# SunnyBuddy.net
KiCad netlist of a schematic drawn in EAGLE
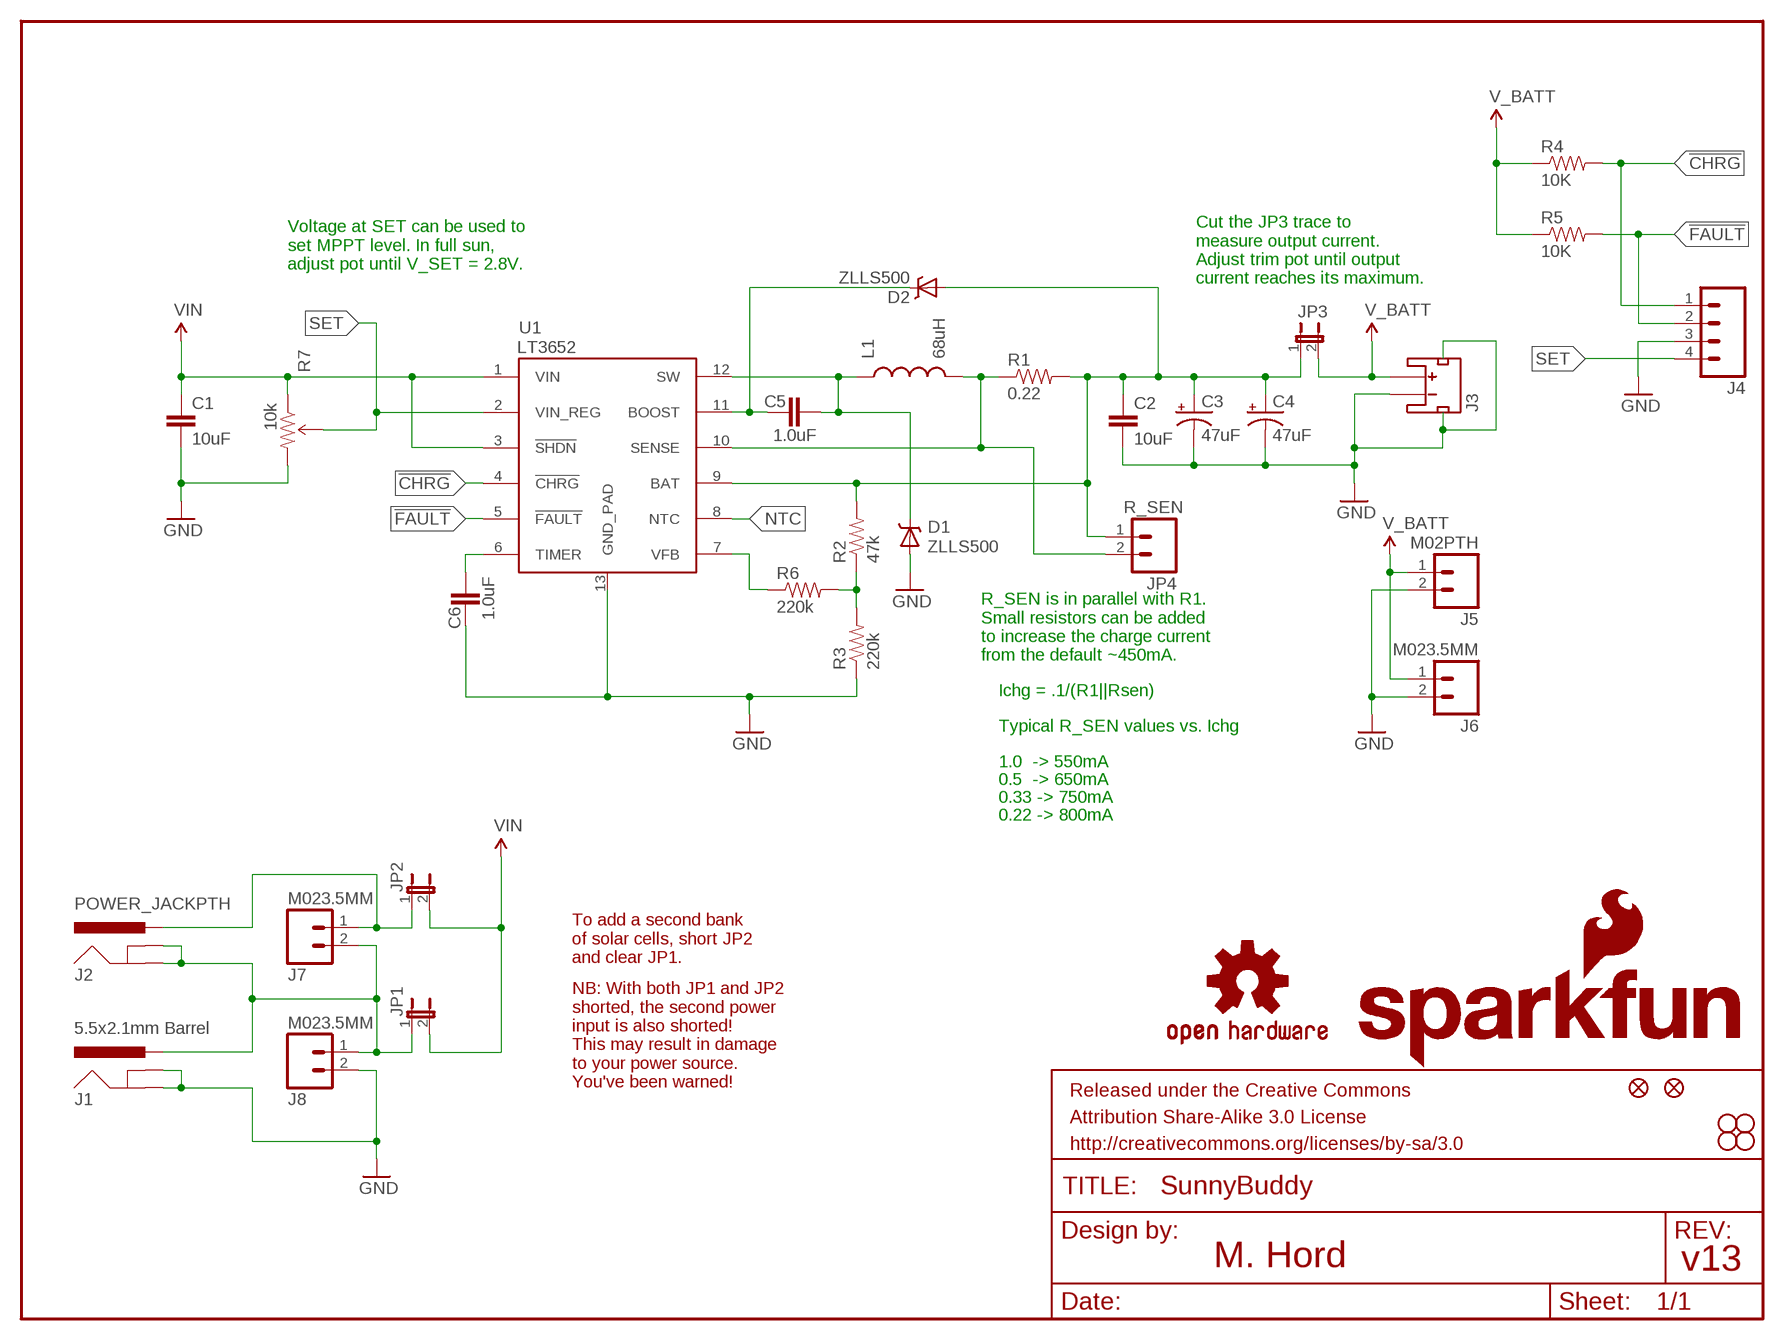
[diagram p0: schematic, sheet 1]

(export (version "E")
  (design (tool "Eeschema 10.0.6"))
  (components
    (comp (ref "C1")
      (value "10uF")
      (footprint "eagle-import:1210")
      (libsource (lib "eagle-import") (part "10UF50V20%(1210)"))
    )
    (comp (ref "C2")
      (value "10uF")
      (footprint "eagle-import:1206")
      (libsource (lib "eagle-import") (part "10UF-6.3V-20%(1206)"))
    )
    (comp (ref "C3")
      (value "47uF")
      (footprint "eagle-import:EIA3528")
      (libsource (lib "eagle-import") (part "47UF-TANT"))
    )
    (comp (ref "C4")
      (value "47uF")
      (footprint "eagle-import:EIA3528")
      (libsource (lib "eagle-import") (part "47UF-TANT"))
    )
    (comp (ref "C5")
      (value "1.0uF")
      (footprint "eagle-import:0603-CAP")
      (libsource (lib "eagle-import") (part "1.0UF-16V-10%(0603)"))
    )
    (comp (ref "C6")
      (value "1.0uF")
      (footprint "eagle-import:0603-CAP")
      (libsource (lib "eagle-import") (part "1.0UF-16V-10%(0603)"))
    )
    (comp (ref "D1")
      (value "ZLLS500")
      (footprint "eagle-import:SOT23")
      (libsource (lib "eagle-import") (part "ZLLS500ZLLS500"))
    )
    (comp (ref "D2")
      (value "ZLLS500")
      (footprint "eagle-import:SOT23")
      (libsource (lib "eagle-import") (part "ZLLS500ZLLS500"))
    )
    (comp (ref "FID1")
      (value "FIDUCIAL1X2")
      (footprint "eagle-import:FIDUCIAL-1X2")
      (libsource (lib "eagle-import") (part "FIDUCIAL1X2"))
    )
    (comp (ref "FID2")
      (value "FIDUCIAL1X2")
      (footprint "eagle-import:FIDUCIAL-1X2")
      (libsource (lib "eagle-import") (part "FIDUCIAL1X2"))
    )
    (comp (ref "FRAME1")
      (value "FRAME-LETTER")
      (footprint "eagle-import:CREATIVE_COMMONS")
      (libsource (lib "eagle-import") (part "FRAME-LETTER"))
    )
    (comp (ref "J1")
      (value "5.5x2.1mm Barrel")
      (footprint "eagle-import:POWER_JACK_SMD")
      (libsource (lib "eagle-import") (part "POWER_JACKSMD"))
    )
    (comp (ref "J2")
      (value "POWER_JACKPTH")
      (footprint "eagle-import:POWER_JACK_PTH")
      (libsource (lib "eagle-import") (part "POWER_JACKPTH"))
    )
    (comp (ref "J3")
      (value "JST_2MM_MALE")
      (footprint "eagle-import:JST-2-SMD")
      (libsource (lib "eagle-import") (part "JST_2MM_MALE"))
    )
    (comp (ref "J4")
      (value "M04PTH")
      (footprint "eagle-import:1X04")
      (libsource (lib "eagle-import") (part "M04PTH"))
    )
    (comp (ref "J5")
      (value "M02PTH")
      (footprint "eagle-import:1X02")
      (libsource (lib "eagle-import") (part "M02PTH"))
    )
    (comp (ref "J6")
      (value "M023.5MM")
      (footprint "eagle-import:SCREWTERMINAL-3.5MM-2")
      (libsource (lib "eagle-import") (part "M023.5MM"))
    )
    (comp (ref "J7")
      (value "M023.5MM")
      (footprint "eagle-import:SCREWTERMINAL-3.5MM-2")
      (libsource (lib "eagle-import") (part "M023.5MM"))
    )
    (comp (ref "J8")
      (value "M023.5MM")
      (footprint "eagle-import:SCREWTERMINAL-3.5MM-2")
      (libsource (lib "eagle-import") (part "M023.5MM"))
    )
    (comp (ref "JP1")
      (value "JUMPER-2SMD-NC")
      (footprint "eagle-import:SJ_2S")
      (libsource (lib "eagle-import") (part "JUMPER-2SMD-NC"))
    )
    (comp (ref "JP2")
      (value "JUMPER-2SMD-NO")
      (footprint "eagle-import:SJ_2S-NO")
      (libsource (lib "eagle-import") (part "JUMPER-2SMD-NO"))
    )
    (comp (ref "JP3")
      (value "JUMPER-PTH-2-NC")
      (footprint "eagle-import:PTH-JUMPER-NC_BOTTOM_NO_SILK")
      (libsource (lib "eagle-import") (part "JUMPER-PTH-2-NC"))
    )
    (comp (ref "JP4")
      (value "R_SEN")
      (footprint "eagle-import:1X02")
      (libsource (lib "eagle-import") (part "M02PTH"))
    )
    (comp (ref "L1")
      (value "68uH")
      (footprint "eagle-import:CR75")
      (libsource (lib "eagle-import") (part "INDUCTOR68UH-1A"))
    )
    (comp (ref "LOGO1")
      (value "SFE_LOGO_NAME_FLAME.2_INCH")
      (footprint "eagle-import:SFE_LOGO_NAME_FLAME_.2")
      (libsource (lib "eagle-import") (part "SFE_LOGO_NAME_FLAME.2_INCH"))
    )
    (comp (ref "LOGO2")
      (value "OSHW-LOGOM")
      (footprint "eagle-import:OSHW-LOGO-M")
      (libsource (lib "eagle-import") (part "OSHW-LOGOM"))
    )
    (comp (ref "LOGO3")
      (value "OSHW-LOGOS")
      (footprint "eagle-import:OSHW-LOGO-S")
      (libsource (lib "eagle-import") (part "OSHW-LOGOS"))
    )
    (comp (ref "LOGO4")
      (value "SFE_LOGO_NAME_FLAME.3_INCH")
      (footprint "eagle-import:SFE_LOGO_NAME_FLAME_.3")
      (libsource (lib "eagle-import") (part "SFE_LOGO_NAME_FLAME.3_INCH"))
    )
    (comp (ref "R1")
      (value "0.22")
      (footprint "eagle-import:0805")
      (libsource (lib "eagle-import") (part "0.22OHM1/4W1%(0805)"))
    )
    (comp (ref "R2")
      (value "47k")
      (footprint "eagle-import:0603-RES")
      (libsource (lib "eagle-import") (part "47KOHM1/10W1%(0603)"))
    )
    (comp (ref "R3")
      (value "220k")
      (footprint "eagle-import:0603-RES")
      (libsource (lib "eagle-import") (part "220KOHM1/10W1%(0603)"))
    )
    (comp (ref "R4")
      (value "10K")
      (footprint "eagle-import:0603-RES")
      (libsource (lib "eagle-import") (part "10KOHM1/10W1%(0603)0603"))
    )
    (comp (ref "R5")
      (value "10K")
      (footprint "eagle-import:0603-RES")
      (libsource (lib "eagle-import") (part "10KOHM1/10W1%(0603)0603"))
    )
    (comp (ref "R6")
      (value "220k")
      (footprint "eagle-import:0603-RES")
      (libsource (lib "eagle-import") (part "220KOHM1/10W1%(0603)"))
    )
    (comp (ref "R7")
      (value "10k")
      (footprint "eagle-import:TRIMPOT-3MM")
      (libsource (lib "eagle-import") (part "TRIMPOTRES-09285"))
    )
    (comp (ref "STANDOFF1")
      (value "STAND-OFF")
      (footprint "eagle-import:STAND-OFF")
      (libsource (lib "eagle-import") (part "STAND-OFF"))
    )
    (comp (ref "STANDOFF2")
      (value "STAND-OFF")
      (footprint "eagle-import:STAND-OFF")
      (libsource (lib "eagle-import") (part "STAND-OFF"))
    )
    (comp (ref "STANDOFF3")
      (value "STAND-OFF")
      (footprint "eagle-import:STAND-OFF")
      (libsource (lib "eagle-import") (part "STAND-OFF"))
    )
    (comp (ref "STANDOFF4")
      (value "STAND-OFF")
      (footprint "eagle-import:STAND-OFF")
      (libsource (lib "eagle-import") (part "STAND-OFF"))
    )
    (comp (ref "U1")
      (value "LT3652")
      (footprint "eagle-import:MSOP-12_GND")
      (libsource (lib "eagle-import") (part "LT3652"))
    )
  )
  (nets
    (net (code "1") (name "/~{CHRG}") (class "Default")
      (node (ref "J4") (pin "1") (pinfunction "1_1") (pintype "passive"))
      (node (ref "R4") (pin "2") (pinfunction "2_2") (pintype "passive"))
      (node (ref "U1") (pin "4") (pinfunction "~{CHRG}_4") (pintype "bidirectional"))
    )
    (net (code "2") (name "/~{FAULT}") (class "Default")
      (node (ref "J4") (pin "2") (pinfunction "2_2") (pintype "passive"))
      (node (ref "R5") (pin "2") (pinfunction "2_2") (pintype "passive"))
      (node (ref "U1") (pin "5") (pinfunction "~{FAULT}_5") (pintype "bidirectional"))
    )
    (net (code "3") (name "GND") (class "Default")
      (node (ref "C1") (pin "2") (pinfunction "2_2") (pintype "passive"))
      (node (ref "C2") (pin "2") (pinfunction "2_2") (pintype "passive"))
      (node (ref "C3") (pin "C") (pinfunction "-_C") (pintype "passive"))
      (node (ref "C4") (pin "C") (pinfunction "-_C") (pintype "passive"))
      (node (ref "C6") (pin "1") (pinfunction "1_1") (pintype "passive"))
      (node (ref "D1") (pin "1") (pinfunction "A_1") (pintype "passive"))
      (node (ref "J1") (pin "GND") (pinfunction "GNDBREAK_GND") (pintype "bidirectional"))
      (node (ref "J1") (pin "P$4") (pinfunction "GND_P$4") (pintype "bidirectional"))
      (node (ref "J3") (pin "1") (pinfunction "-_1") (pintype "bidirectional"))
      (node (ref "J3") (pin "NC1") (pinfunction "PAD1_NC1") (pintype "bidirectional"))
      (node (ref "J3") (pin "NC2") (pinfunction "PAD2_NC2") (pintype "bidirectional"))
      (node (ref "J4") (pin "3") (pinfunction "3_3") (pintype "passive"))
      (node (ref "J5") (pin "2") (pinfunction "2_2") (pintype "passive"))
      (node (ref "J6") (pin "2") (pinfunction "2_2") (pintype "passive"))
      (node (ref "J8") (pin "2") (pinfunction "2_2") (pintype "passive"))
      (node (ref "R3") (pin "1") (pinfunction "1_1") (pintype "passive"))
      (node (ref "R7") (pin "3") (pinfunction "CW_3") (pintype "passive"))
      (node (ref "U1") (pin "13") (pinfunction "GND_PAD_13") (pintype "bidirectional"))
    )
    (net (code "4") (name "NTC") (class "Default")
      (node (ref "U1") (pin "8") (pinfunction "NTC_8") (pintype "bidirectional"))
    )
    (net (code "5") (name "Net-(C3-+)") (class "Default")
      (node (ref "C2") (pin "1") (pinfunction "1_1") (pintype "passive"))
      (node (ref "C3") (pin "A") (pinfunction "+_A") (pintype "passive"))
      (node (ref "C4") (pin "A") (pinfunction "+_A") (pintype "passive"))
      (node (ref "D2") (pin "1") (pinfunction "A_1") (pintype "passive"))
      (node (ref "JP3") (pin "1") (pinfunction "1_1") (pintype "passive"))
      (node (ref "JP4") (pin "1") (pinfunction "1_1") (pintype "passive"))
      (node (ref "R1") (pin "2") (pinfunction "2_2") (pintype "passive"))
      (node (ref "R2") (pin "2") (pinfunction "2_2") (pintype "passive"))
      (node (ref "U1") (pin "9") (pinfunction "BAT_9") (pintype "bidirectional"))
    )
    (net (code "6") (name "Net-(D1-C)") (class "Default")
      (node (ref "C5") (pin "2") (pinfunction "2_2") (pintype "passive"))
      (node (ref "D1") (pin "3") (pinfunction "C_3") (pintype "passive"))
      (node (ref "L1") (pin "P$1") (pinfunction "1_P$1") (pintype "passive"))
      (node (ref "U1") (pin "12") (pinfunction "SW_12") (pintype "bidirectional"))
    )
    (net (code "7") (name "Net-(D2-C)") (class "Default")
      (node (ref "C5") (pin "1") (pinfunction "1_1") (pintype "passive"))
      (node (ref "D2") (pin "3") (pinfunction "C_3") (pintype "passive"))
      (node (ref "U1") (pin "11") (pinfunction "BOOST_11") (pintype "bidirectional"))
    )
    (net (code "8") (name "Net-(J1-PWR)") (class "Default")
      (node (ref "J1") (pin "VIN0") (pinfunction "PWR_VIN0") (pintype "bidirectional"))
      (node (ref "J2") (pin "GND") (pinfunction "GND_GND") (pintype "bidirectional"))
      (node (ref "J2") (pin "GNDBREAK") (pinfunction "GNDBREAK_GNDBREAK") (pintype "bidirectional"))
      (node (ref "J7") (pin "2") (pinfunction "2_2") (pintype "passive"))
      (node (ref "J8") (pin "1") (pinfunction "1_1") (pintype "passive"))
      (node (ref "JP1") (pin "1") (pinfunction "1_1") (pintype "passive"))
    )
    (net (code "9") (name "Net-(J2-PadPWR)") (class "Default")
      (node (ref "J2") (pin "PWR") (pinfunction "PWR_PWR") (pintype "bidirectional"))
      (node (ref "J7") (pin "1") (pinfunction "1_1") (pintype "passive"))
      (node (ref "JP2") (pin "1") (pinfunction "1_1") (pintype "passive"))
    )
    (net (code "10") (name "Net-(L1-2)") (class "Default")
      (node (ref "JP4") (pin "2") (pinfunction "2_2") (pintype "passive"))
      (node (ref "L1") (pin "P$2") (pinfunction "2_P$2") (pintype "passive"))
      (node (ref "R1") (pin "1") (pinfunction "1_1") (pintype "passive"))
      (node (ref "U1") (pin "10") (pinfunction "SENSE_10") (pintype "bidirectional"))
    )
    (net (code "11") (name "Net-(R2-Pad1)") (class "Default")
      (node (ref "R2") (pin "1") (pinfunction "1_1") (pintype "passive"))
      (node (ref "R3") (pin "2") (pinfunction "2_2") (pintype "passive"))
      (node (ref "R6") (pin "2") (pinfunction "2_2") (pintype "passive"))
    )
    (net (code "12") (name "Net-(U1-TIMER)") (class "Default")
      (node (ref "C6") (pin "2") (pinfunction "2_2") (pintype "passive"))
      (node (ref "U1") (pin "6") (pinfunction "TIMER_6") (pintype "bidirectional"))
    )
    (net (code "13") (name "Net-(U1-VFB)") (class "Default")
      (node (ref "R6") (pin "1") (pinfunction "1_1") (pintype "passive"))
      (node (ref "U1") (pin "7") (pinfunction "VFB_7") (pintype "bidirectional"))
    )
    (net (code "14") (name "SET") (class "Default")
      (node (ref "J4") (pin "4") (pinfunction "4_4") (pintype "passive"))
      (node (ref "R7") (pin "2") (pinfunction "WIPER_2") (pintype "passive"))
      (node (ref "U1") (pin "2") (pinfunction "VIN_REG_2") (pintype "bidirectional"))
    )
    (net (code "15") (name "VIN") (class "Default")
      (node (ref "C1") (pin "1") (pinfunction "1_1") (pintype "passive"))
      (node (ref "JP1") (pin "2") (pinfunction "2_2") (pintype "passive"))
      (node (ref "JP2") (pin "2") (pinfunction "2_2") (pintype "passive"))
      (node (ref "R7") (pin "1") (pinfunction "CCW_1") (pintype "passive"))
      (node (ref "U1") (pin "1") (pinfunction "VIN_1") (pintype "bidirectional"))
      (node (ref "U1") (pin "3") (pinfunction "~{SHDN}_3") (pintype "bidirectional"))
    )
    (net (code "16") (name "V_BATT") (class "Default")
      (node (ref "J3") (pin "2") (pinfunction "+_2") (pintype "bidirectional"))
      (node (ref "J5") (pin "1") (pinfunction "1_1") (pintype "passive"))
      (node (ref "J6") (pin "1") (pinfunction "1_1") (pintype "passive"))
      (node (ref "JP3") (pin "2") (pinfunction "2_2") (pintype "passive"))
      (node (ref "R4") (pin "1") (pinfunction "1_1") (pintype "passive"))
      (node (ref "R5") (pin "1") (pinfunction "1_1") (pintype "passive"))
    )
  )
)
